# BrunnenwasserSensor.net
KiCad netlist of a schematic drawn in EAGLE
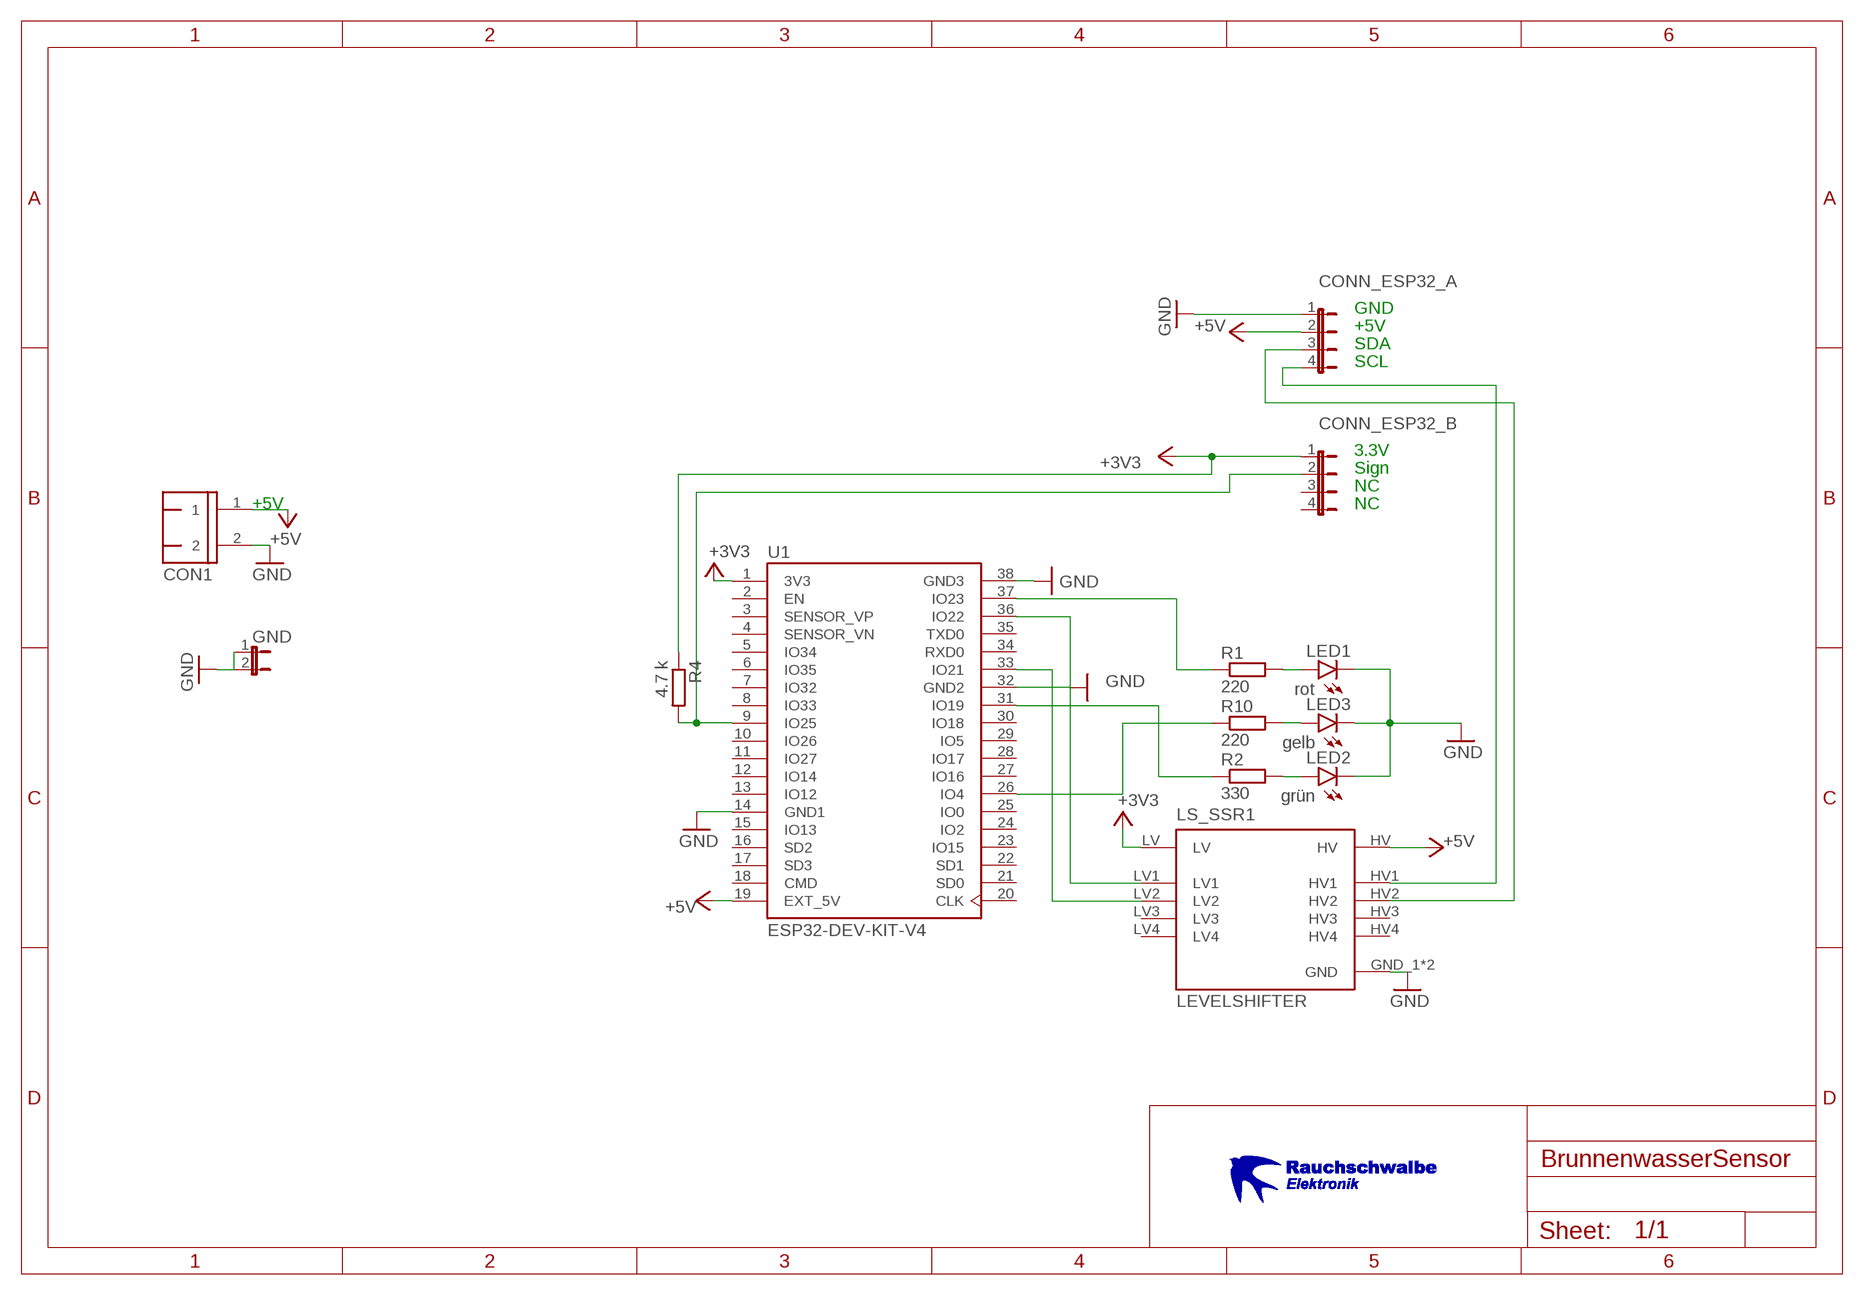
[diagram p0: schematic, sheet 1]

(export (version "E")
  (design (tool "Eeschema 10.0.6"))
  (components
    (comp (ref "CON1")
      (value "WAGO-500-2")
      (footprint "eagle-import:WAGO-500-2")
      (fields (field (name "MPN") "237-102"))
      (libsource (lib "eagle-import") (part "WAGO-500-2"))
    )
    (comp (ref "CONN_ESP32_A")
      (value "JP4E")
      (footprint "eagle-import:JP4")
      (libsource (lib "eagle-import") (part "JP4E"))
    )
    (comp (ref "CONN_ESP32_B")
      (value "JP4E")
      (footprint "eagle-import:JP4")
      (libsource (lib "eagle-import") (part "JP4E"))
    )
    (comp (ref "GND")
      (value "JP1E")
      (footprint "eagle-import:JP1")
      (libsource (lib "eagle-import") (part "JP1E"))
    )
    (comp (ref "LED1")
      (value "rot")
      (footprint "eagle-import:LED3MM")
      (libsource (lib "eagle-import") (part "LED3MM"))
    )
    (comp (ref "LED2")
      (value "grün")
      (footprint "eagle-import:LED3MM")
      (libsource (lib "eagle-import") (part "LED3MM"))
    )
    (comp (ref "LED3")
      (value "gelb")
      (footprint "eagle-import:LED3MM")
      (libsource (lib "eagle-import") (part "LED3MM"))
    )
    (comp (ref "LS_SSR1")
      (value "LEVELSHIFTER")
      (footprint "eagle-import:LEVELSHIFTER")
      (fields (field (name "MF") "SparkFun") (field (name "MP") "BOB-12009"))
      (libsource (lib "eagle-import") (part "LEVELSHIFTER"))
    )
    (comp (ref "R1")
      (value "220")
      (footprint "eagle-import:0207_10")
      (libsource (lib "eagle-import") (part "R_10MM0207/10"))
    )
    (comp (ref "R2")
      (value "330")
      (footprint "eagle-import:0207_10")
      (libsource (lib "eagle-import") (part "R_10MM0207/10"))
    )
    (comp (ref "R4")
      (value "4.7 k")
      (footprint "eagle-import:0207_10")
      (libsource (lib "eagle-import") (part "R_10MM0207/10"))
    )
    (comp (ref "R10")
      (value "220")
      (footprint "eagle-import:0207_10")
      (libsource (lib "eagle-import") (part "R_10MM0207/10"))
    )
    (comp (ref "U$1")
      (value "LOGO_RAUCHSCHWALBE")
      (footprint "eagle-import:LOGO_RAUCHSCHWALBE")
      (libsource (lib "eagle-import") (part "LOGO_RAUCHSCHWALBE"))
    )
    (comp (ref "U1")
      (value "ESP32-DEV-KIT-V4")
      (footprint "eagle-import:ESP32-DEV-KIT-V4")
      (fields (field (name "MF") "Espressif Systems") (field (name "MP") "ESP32-DEVKITC"))
      (libsource (lib "eagle-import") (part "ESP32-DEV-KIT-V4"))
    )
  )
  (nets
    (net (code "1") (name "+3V3") (class "Default")
      (node (ref "CONN_ESP32_B") (pin "1") (pinfunction "1_1") (pintype "passive"))
      (node (ref "LS_SSR1") (pin "LV") (pinfunction "LV_LV") (pintype "bidirectional"))
      (node (ref "R4") (pin "1") (pinfunction "1_1") (pintype "passive"))
      (node (ref "U1") (pin "1") (pinfunction "3V3_1") (pintype "power_in"))
    )
    (net (code "2") (name "+5V") (class "Default")
      (node (ref "CON1") (pin "1") (pinfunction "1_1") (pintype "passive"))
      (node (ref "CONN_ESP32_A") (pin "2") (pinfunction "2_2") (pintype "passive"))
      (node (ref "LS_SSR1") (pin "HV") (pinfunction "HV_HV") (pintype "bidirectional"))
      (node (ref "U1") (pin "19") (pinfunction "EXT_5V_19") (pintype "power_in"))
    )
    (net (code "3") (name "GND") (class "Default")
      (node (ref "CON1") (pin "2") (pinfunction "2_2") (pintype "passive"))
      (node (ref "CONN_ESP32_A") (pin "1") (pinfunction "1_1") (pintype "passive"))
      (node (ref "GND") (pin "1") (pinfunction "1_1") (pintype "passive"))
      (node (ref "GND") (pin "2") (pinfunction "2_2") (pintype "passive"))
      (node (ref "LED1") (pin "K") (pinfunction "C_K") (pintype "passive"))
      (node (ref "LED2") (pin "K") (pinfunction "C_K") (pintype "passive"))
      (node (ref "LED3") (pin "K") (pinfunction "C_K") (pintype "passive"))
      (node (ref "LS_SSR1") (pin "GND_1") (pinfunction "GND_GND_1") (pintype "power_in"))
      (node (ref "LS_SSR1") (pin "GND_2") (pinfunction "GND_GND_2") (pintype "power_in"))
      (node (ref "U1") (pin "14") (pinfunction "GND1_14") (pintype "power_in"))
      (node (ref "U1") (pin "32") (pinfunction "GND2_32") (pintype "power_in"))
      (node (ref "U1") (pin "38") (pinfunction "GND3_38") (pintype "power_in"))
    )
    (net (code "4") (name "Net-(CONN_ESP32_A-Pad3)") (class "Default")
      (node (ref "CONN_ESP32_A") (pin "3") (pinfunction "3_3") (pintype "passive"))
      (node (ref "LS_SSR1") (pin "HV2") (pinfunction "HV2_HV2") (pintype "bidirectional"))
    )
    (net (code "5") (name "Net-(CONN_ESP32_A-Pad4)") (class "Default")
      (node (ref "CONN_ESP32_A") (pin "4") (pinfunction "4_4") (pintype "passive"))
      (node (ref "LS_SSR1") (pin "HV1") (pinfunction "HV1_HV1") (pintype "bidirectional"))
    )
    (net (code "6") (name "Net-(LED1-PadA)") (class "Default")
      (node (ref "LED1") (pin "A") (pinfunction "A_A") (pintype "passive"))
      (node (ref "R1") (pin "2") (pinfunction "2_2") (pintype "passive"))
    )
    (net (code "7") (name "Net-(LED2-PadA)") (class "Default")
      (node (ref "LED2") (pin "A") (pinfunction "A_A") (pintype "passive"))
      (node (ref "R2") (pin "2") (pinfunction "2_2") (pintype "passive"))
    )
    (net (code "8") (name "Net-(LED3-PadA)") (class "Default")
      (node (ref "LED3") (pin "A") (pinfunction "A_A") (pintype "passive"))
      (node (ref "R10") (pin "2") (pinfunction "2_2") (pintype "passive"))
    )
    (net (code "9") (name "Net-(U1-IO4)") (class "Default")
      (node (ref "R10") (pin "1") (pinfunction "1_1") (pintype "passive"))
      (node (ref "U1") (pin "26") (pinfunction "IO4_26") (pintype "bidirectional"))
    )
    (net (code "10") (name "Net-(U1-IO19)") (class "Default")
      (node (ref "R2") (pin "1") (pinfunction "1_1") (pintype "passive"))
      (node (ref "U1") (pin "31") (pinfunction "IO19_31") (pintype "bidirectional"))
    )
    (net (code "11") (name "Net-(U1-IO21)") (class "Default")
      (node (ref "LS_SSR1") (pin "LV2") (pinfunction "LV2_LV2") (pintype "bidirectional"))
      (node (ref "U1") (pin "33") (pinfunction "IO21_33") (pintype "bidirectional"))
    )
    (net (code "12") (name "Net-(U1-IO22)") (class "Default")
      (node (ref "LS_SSR1") (pin "LV1") (pinfunction "LV1_LV1") (pintype "bidirectional"))
      (node (ref "U1") (pin "36") (pinfunction "IO22_36") (pintype "bidirectional"))
    )
    (net (code "13") (name "Net-(U1-IO23)") (class "Default")
      (node (ref "R1") (pin "1") (pinfunction "1_1") (pintype "passive"))
      (node (ref "U1") (pin "37") (pinfunction "IO23_37") (pintype "bidirectional"))
    )
    (net (code "14") (name "Net-(U1-IO25)") (class "Default")
      (node (ref "CONN_ESP32_B") (pin "2") (pinfunction "2_2") (pintype "passive"))
      (node (ref "R4") (pin "2") (pinfunction "2_2") (pintype "passive"))
      (node (ref "U1") (pin "9") (pinfunction "IO25_9") (pintype "bidirectional"))
    )
    (net (code "15") (name "unconnected-(CONN_ESP32_B-Pad3)") (class "Default")
      (node (ref "CONN_ESP32_B") (pin "3") (pinfunction "3_3") (pintype "passive"))
    )
    (net (code "16") (name "unconnected-(CONN_ESP32_B-Pad4)") (class "Default")
      (node (ref "CONN_ESP32_B") (pin "4") (pinfunction "4_4") (pintype "passive"))
    )
    (net (code "17") (name "unconnected-(LS_SSR1-PadHV3)") (class "Default")
      (node (ref "LS_SSR1") (pin "HV3") (pinfunction "HV3_HV3") (pintype "bidirectional"))
    )
    (net (code "18") (name "unconnected-(LS_SSR1-PadHV4)") (class "Default")
      (node (ref "LS_SSR1") (pin "HV4") (pinfunction "HV4_HV4") (pintype "bidirectional"))
    )
    (net (code "19") (name "unconnected-(LS_SSR1-PadLV3)") (class "Default")
      (node (ref "LS_SSR1") (pin "LV3") (pinfunction "LV3_LV3") (pintype "bidirectional"))
    )
    (net (code "20") (name "unconnected-(LS_SSR1-PadLV4)") (class "Default")
      (node (ref "LS_SSR1") (pin "LV4") (pinfunction "LV4_LV4") (pintype "bidirectional"))
    )
    (net (code "21") (name "unconnected-(U1-CLK-Pad20)") (class "Default")
      (node (ref "U1") (pin "20") (pinfunction "CLK_20") (pintype "input"))
    )
    (net (code "22") (name "unconnected-(U1-CMD-Pad18)") (class "Default")
      (node (ref "U1") (pin "18") (pinfunction "CMD_18") (pintype "bidirectional"))
    )
    (net (code "23") (name "unconnected-(U1-EN-Pad2)") (class "Default")
      (node (ref "U1") (pin "2") (pinfunction "EN_2") (pintype "input"))
    )
    (net (code "24") (name "unconnected-(U1-IO0-Pad25)") (class "Default")
      (node (ref "U1") (pin "25") (pinfunction "IO0_25") (pintype "bidirectional"))
    )
    (net (code "25") (name "unconnected-(U1-IO2-Pad24)") (class "Default")
      (node (ref "U1") (pin "24") (pinfunction "IO2_24") (pintype "bidirectional"))
    )
    (net (code "26") (name "unconnected-(U1-IO5-Pad29)") (class "Default")
      (node (ref "U1") (pin "29") (pinfunction "IO5_29") (pintype "bidirectional"))
    )
    (net (code "27") (name "unconnected-(U1-IO12-Pad13)") (class "Default")
      (node (ref "U1") (pin "13") (pinfunction "IO12_13") (pintype "bidirectional"))
    )
    (net (code "28") (name "unconnected-(U1-IO13-Pad15)") (class "Default")
      (node (ref "U1") (pin "15") (pinfunction "IO13_15") (pintype "bidirectional"))
    )
    (net (code "29") (name "unconnected-(U1-IO14-Pad12)") (class "Default")
      (node (ref "U1") (pin "12") (pinfunction "IO14_12") (pintype "bidirectional"))
    )
    (net (code "30") (name "unconnected-(U1-IO15-Pad23)") (class "Default")
      (node (ref "U1") (pin "23") (pinfunction "IO15_23") (pintype "bidirectional"))
    )
    (net (code "31") (name "unconnected-(U1-IO16-Pad27)") (class "Default")
      (node (ref "U1") (pin "27") (pinfunction "IO16_27") (pintype "bidirectional"))
    )
    (net (code "32") (name "unconnected-(U1-IO17-Pad28)") (class "Default")
      (node (ref "U1") (pin "28") (pinfunction "IO17_28") (pintype "bidirectional"))
    )
    (net (code "33") (name "unconnected-(U1-IO18-Pad30)") (class "Default")
      (node (ref "U1") (pin "30") (pinfunction "IO18_30") (pintype "bidirectional"))
    )
    (net (code "34") (name "unconnected-(U1-IO26-Pad10)") (class "Default")
      (node (ref "U1") (pin "10") (pinfunction "IO26_10") (pintype "bidirectional"))
    )
    (net (code "35") (name "unconnected-(U1-IO27-Pad11)") (class "Default")
      (node (ref "U1") (pin "11") (pinfunction "IO27_11") (pintype "bidirectional"))
    )
    (net (code "36") (name "unconnected-(U1-IO32-Pad7)") (class "Default")
      (node (ref "U1") (pin "7") (pinfunction "IO32_7") (pintype "bidirectional"))
    )
    (net (code "37") (name "unconnected-(U1-IO33-Pad8)") (class "Default")
      (node (ref "U1") (pin "8") (pinfunction "IO33_8") (pintype "bidirectional"))
    )
    (net (code "38") (name "unconnected-(U1-IO34-Pad5)") (class "Default")
      (node (ref "U1") (pin "5") (pinfunction "IO34_5") (pintype "bidirectional"))
    )
    (net (code "39") (name "unconnected-(U1-IO35-Pad6)") (class "Default")
      (node (ref "U1") (pin "6") (pinfunction "IO35_6") (pintype "bidirectional"))
    )
    (net (code "40") (name "unconnected-(U1-RXD0-Pad34)") (class "Default")
      (node (ref "U1") (pin "34") (pinfunction "RXD0_34") (pintype "input"))
    )
    (net (code "41") (name "unconnected-(U1-SD0-Pad21)") (class "Default")
      (node (ref "U1") (pin "21") (pinfunction "SD0_21") (pintype "bidirectional"))
    )
    (net (code "42") (name "unconnected-(U1-SD1-Pad22)") (class "Default")
      (node (ref "U1") (pin "22") (pinfunction "SD1_22") (pintype "bidirectional"))
    )
    (net (code "43") (name "unconnected-(U1-SD2-Pad16)") (class "Default")
      (node (ref "U1") (pin "16") (pinfunction "SD2_16") (pintype "bidirectional"))
    )
    (net (code "44") (name "unconnected-(U1-SD3-Pad17)") (class "Default")
      (node (ref "U1") (pin "17") (pinfunction "SD3_17") (pintype "bidirectional"))
    )
    (net (code "45") (name "unconnected-(U1-SENSOR_VN-Pad4)") (class "Default")
      (node (ref "U1") (pin "4") (pinfunction "SENSOR_VN_4") (pintype "input"))
    )
    (net (code "46") (name "unconnected-(U1-SENSOR_VP-Pad3)") (class "Default")
      (node (ref "U1") (pin "3") (pinfunction "SENSOR_VP_3") (pintype "input"))
    )
    (net (code "47") (name "unconnected-(U1-TXD0-Pad35)") (class "Default")
      (node (ref "U1") (pin "35") (pinfunction "TXD0_35") (pintype "output"))
    )
  )
)
